# lp-servo12.net
KiCad netlist of a schematic drawn in EAGLE
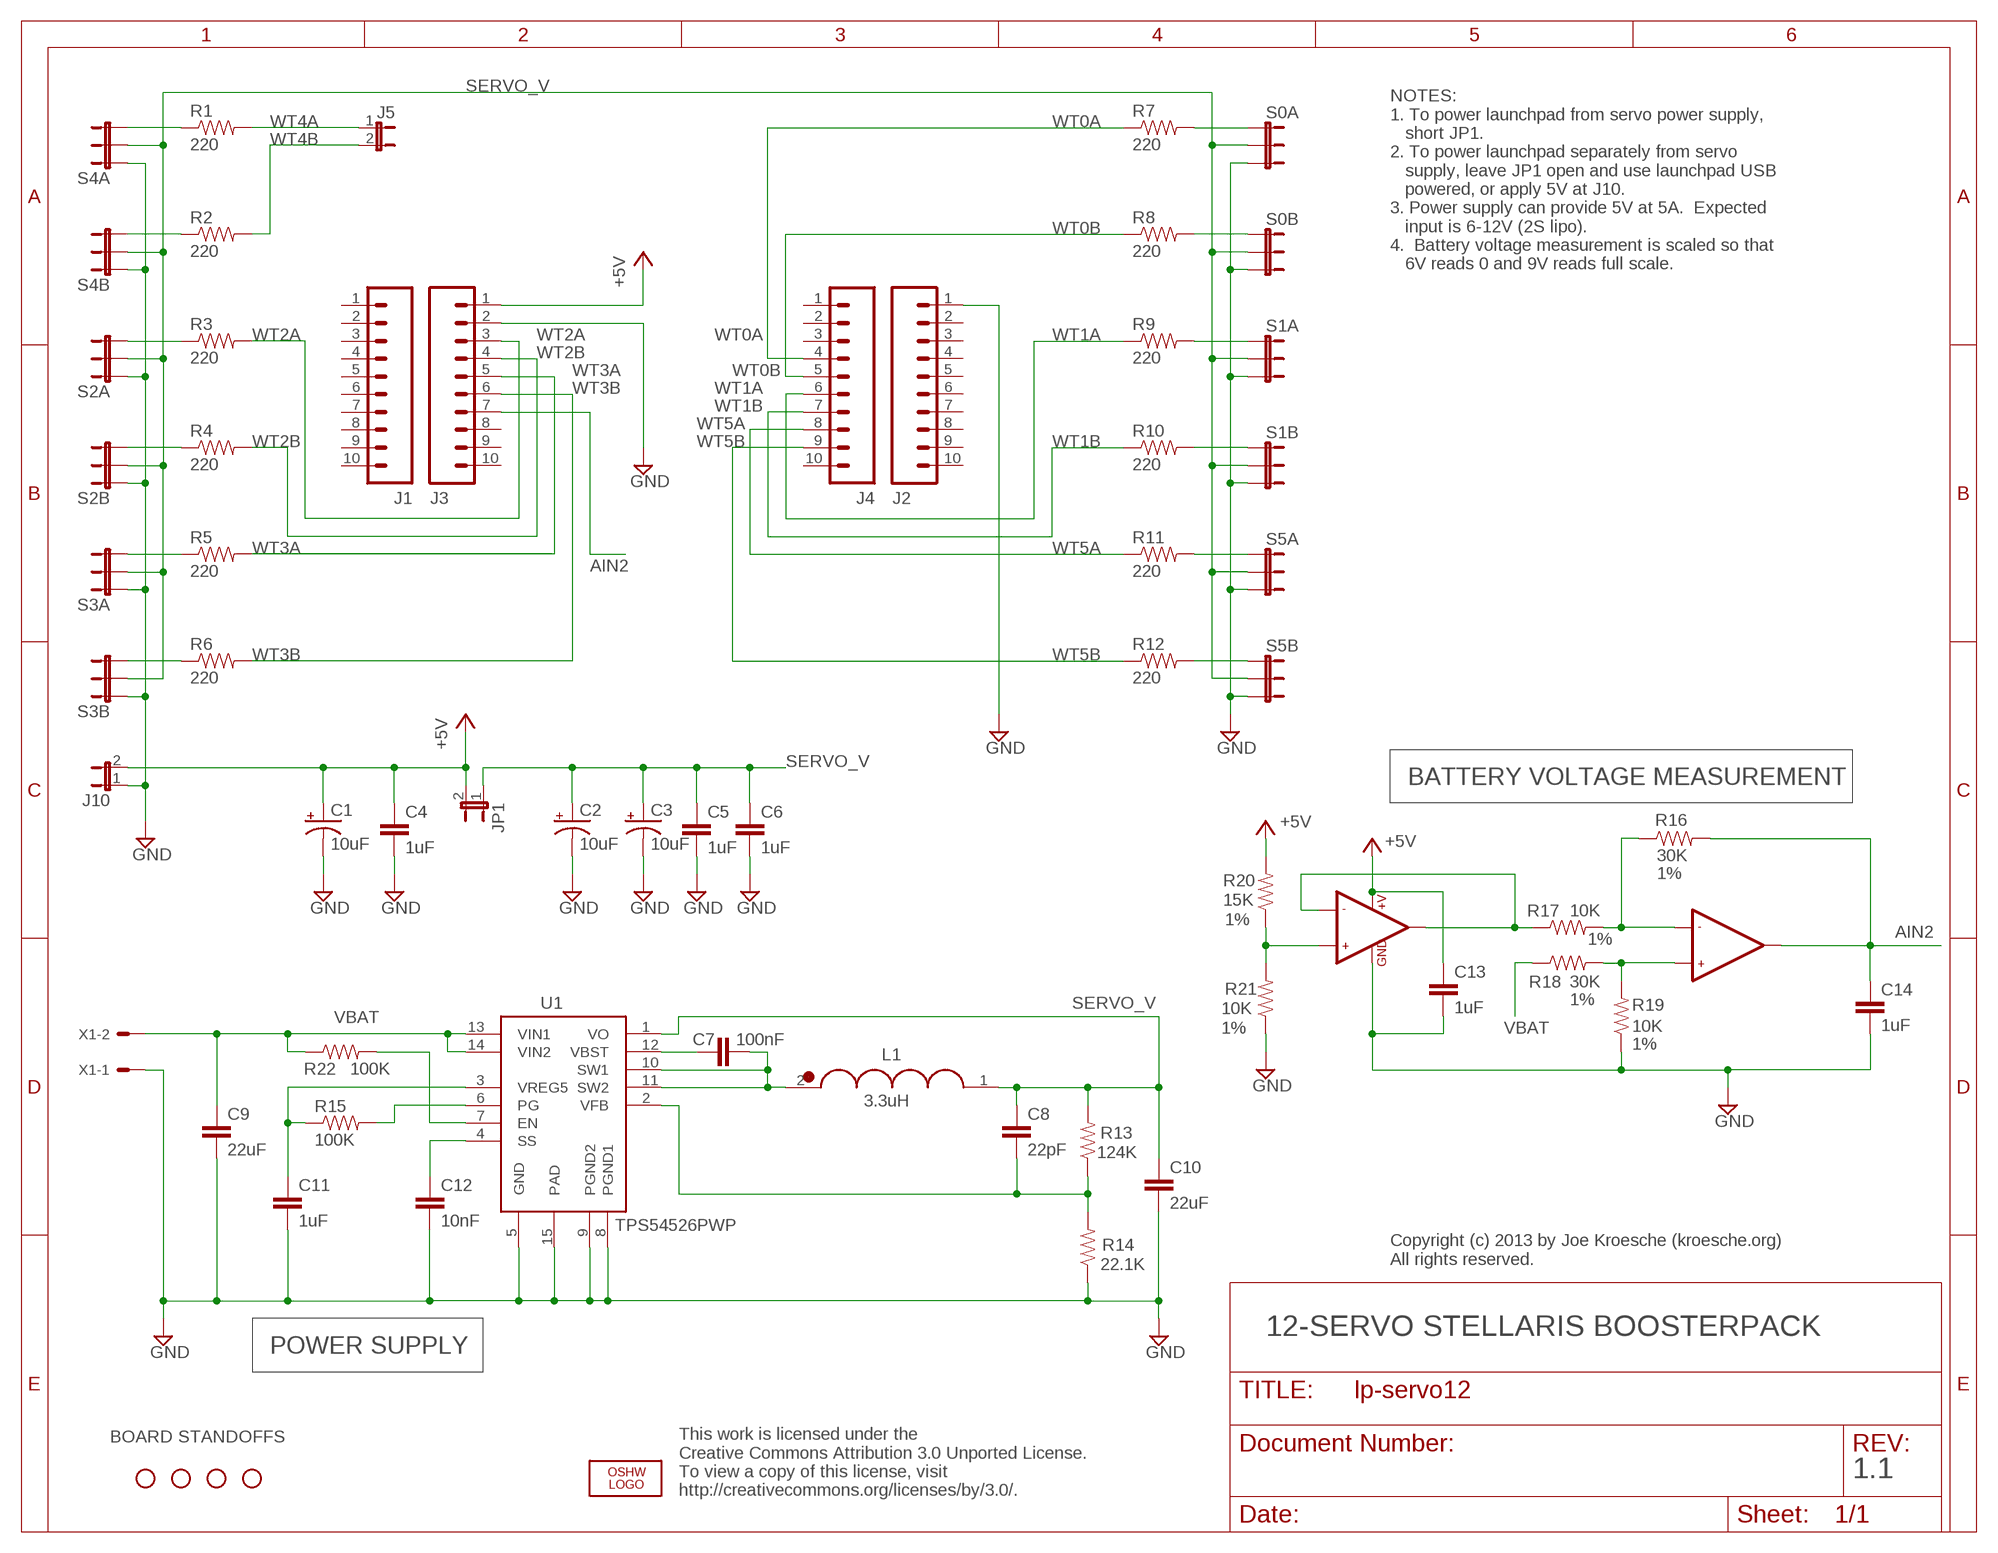
[diagram p0: schematic, sheet 1]

(export (version "E")
  (design (tool "Eeschema 10.0.6"))
  (components
    (comp (ref "C1")
      (value "10uF")
      (footprint "eagle-import:EIA3216")
      (fields (field (name "PARTNO") "CAP_10u_20V_20PCT_1206"))
      (libsource (lib "eagle-import") (part "CAP_POL1206"))
    )
    (comp (ref "C2")
      (value "10uF")
      (footprint "eagle-import:EIA3216")
      (fields (field (name "PARTNO") "CAP_10u_20V_20PCT_1206"))
      (libsource (lib "eagle-import") (part "CAP_POL1206"))
    )
    (comp (ref "C3")
      (value "10uF")
      (footprint "eagle-import:EIA3216")
      (fields (field (name "PARTNO") "CAP_10u_20V_20PCT_1206"))
      (libsource (lib "eagle-import") (part "CAP_POL1206"))
    )
    (comp (ref "C4")
      (value "1uF")
      (footprint "eagle-import:0805")
      (fields (field (name "PARTNO") "CAP_1u_20V_20PCT_0805"))
      (libsource (lib "eagle-import") (part "CAP0805"))
    )
    (comp (ref "C5")
      (value "1uF")
      (footprint "eagle-import:0805")
      (fields (field (name "PARTNO") "CAP_1u_20V_20PCT_0805"))
      (libsource (lib "eagle-import") (part "CAP0805"))
    )
    (comp (ref "C6")
      (value "1uF")
      (footprint "eagle-import:0805")
      (fields (field (name "PARTNO") "CAP_1u_20V_20PCT_0805"))
      (libsource (lib "eagle-import") (part "CAP0805"))
    )
    (comp (ref "C7")
      (value "100nF")
      (footprint "eagle-import:0805")
      (fields (field (name "PARTNO") "CAP_100n_25V_10PCT_0805"))
      (libsource (lib "eagle-import") (part "CAP0805"))
    )
    (comp (ref "C8")
      (value "22pF")
      (footprint "eagle-import:0805")
      (fields (field (name "PARTNO") "CAP_22p_50V_10PCT_0805"))
      (libsource (lib "eagle-import") (part "CAP0805"))
    )
    (comp (ref "C9")
      (value "22uF")
      (footprint "eagle-import:1210")
      (fields (field (name "PARTNO") "CAP_22u_16V_10PCT_1210"))
      (libsource (lib "eagle-import") (part "CAP1210"))
    )
    (comp (ref "C10")
      (value "22uF")
      (footprint "eagle-import:1206")
      (fields (field (name "PARTNO") "CAP_22u_16V_20PCT_1206"))
      (libsource (lib "eagle-import") (part "CAP1206"))
    )
    (comp (ref "C11")
      (value "1uF")
      (footprint "eagle-import:0805")
      (fields (field (name "PARTNO") "CAP_1u_20V_20PCT_0805"))
      (libsource (lib "eagle-import") (part "CAP0805"))
    )
    (comp (ref "C12")
      (value "10nF")
      (footprint "eagle-import:0805")
      (fields (field (name "PARTNO") "CAP_10n_50V_10PCT_0805"))
      (libsource (lib "eagle-import") (part "CAP0805"))
    )
    (comp (ref "C13")
      (value "1uF")
      (footprint "eagle-import:0805")
      (fields (field (name "PARTNO") "CAP_1u_20V_20PCT_0805"))
      (libsource (lib "eagle-import") (part "CAP0805"))
    )
    (comp (ref "C14")
      (value "1uF")
      (footprint "eagle-import:0805")
      (fields (field (name "PARTNO") "CAP_1u_20V_20PCT_0805"))
      (libsource (lib "eagle-import") (part "CAP0805"))
    )
    (comp (ref "J1")
      (value "M10\"")
      (footprint "eagle-import:1X10")
      (fields (field (name "PARTNO") "68002-110HLF"))
      (libsource (lib "eagle-import") (part "M10{dblquote}"))
    )
    (comp (ref "J2")
      (value "M10\"")
      (footprint "eagle-import:1X10")
      (fields (field (name "PARTNO") "68002-110HLF"))
      (libsource (lib "eagle-import") (part "M10{dblquote}"))
    )
    (comp (ref "J3")
      (value "M10\"")
      (footprint "eagle-import:1X10")
      (fields (field (name "PARTNO") "68002-110HLF"))
      (libsource (lib "eagle-import") (part "M10{dblquote}"))
    )
    (comp (ref "J4")
      (value "M10\"")
      (footprint "eagle-import:1X10")
      (fields (field (name "PARTNO") "68002-110HLF"))
      (libsource (lib "eagle-import") (part "M10{dblquote}"))
    )
    (comp (ref "J5")
      (value "JUMPER-2PTH")
      (footprint "eagle-import:1X02")
      (fields (field (name "PARTNO") "68002-202HLF"))
      (libsource (lib "eagle-import") (part "JUMPER-2PTH"))
    )
    (comp (ref "J10")
      (value "JUMPER-2PTH")
      (footprint "eagle-import:1X02")
      (fields (field (name "PARTNO") "68016-402"))
      (libsource (lib "eagle-import") (part "JUMPER-2PTH"))
    )
    (comp (ref "JP1")
      (value "JUMPER-2PTH")
      (footprint "eagle-import:1X02")
      (fields (field (name "PARTNO") "68002-202HLF"))
      (libsource (lib "eagle-import") (part "JUMPER-2PTH"))
    )
    (comp (ref "L1")
      (value "3.3uH")
      (footprint "eagle-import:VISHAY-IHLP3232DZER")
      (fields
        (field (name "MANF") "Vishay/Dale")
        (field (name "MANF#") "IHLP3232DZER3R3M11")
        (field (name "MOUSER#") "70-IHLP3232DZER3R3M11")
        (field (name "PARTNO") "IHLP3232DZER3R3M11")
      )
      (libsource (lib "eagle-import") (part "VISHAY-IHLP-3232DZ-11"))
    )
    (comp (ref "LOGO2")
      (value "OSHW_LOGO_6MILX0200-NT")
      (footprint "eagle-import:OSHW_6X200_NOTEXT")
      (libsource (lib "eagle-import") (part "OSHW_LOGO_6MILX0200-NT"))
    )
    (comp (ref "R1")
      (value "220")
      (footprint "eagle-import:0805")
      (fields (field (name "MANF") "Panasonic") (field (name "PARTNO") "RES_220_20V_10PCT_0805"))
      (libsource (lib "eagle-import") (part "RESISTOR0805-RES"))
    )
    (comp (ref "R2")
      (value "220")
      (footprint "eagle-import:0805")
      (fields (field (name "PARTNO") "RES_220_20V_10PCT_0805"))
      (libsource (lib "eagle-import") (part "RESISTOR0805-RES"))
    )
    (comp (ref "R3")
      (value "220")
      (footprint "eagle-import:0805")
      (fields (field (name "PARTNO") "RES_220_20V_10PCT_0805"))
      (libsource (lib "eagle-import") (part "RESISTOR0805-RES"))
    )
    (comp (ref "R4")
      (value "220")
      (footprint "eagle-import:0805")
      (fields (field (name "PARTNO") "RES_220_20V_10PCT_0805"))
      (libsource (lib "eagle-import") (part "RESISTOR0805-RES"))
    )
    (comp (ref "R5")
      (value "220")
      (footprint "eagle-import:0805")
      (fields (field (name "PARTNO") "RES_220_20V_10PCT_0805"))
      (libsource (lib "eagle-import") (part "RESISTOR0805-RES"))
    )
    (comp (ref "R6")
      (value "220")
      (footprint "eagle-import:0805")
      (fields (field (name "PARTNO") "RES_220_20V_10PCT_0805"))
      (libsource (lib "eagle-import") (part "RESISTOR0805-RES"))
    )
    (comp (ref "R7")
      (value "220")
      (footprint "eagle-import:0805")
      (fields (field (name "PARTNO") "RES_220_20V_10PCT_0805"))
      (libsource (lib "eagle-import") (part "RESISTOR0805-RES"))
    )
    (comp (ref "R8")
      (value "220")
      (footprint "eagle-import:0805")
      (fields (field (name "PARTNO") "RES_220_20V_10PCT_0805"))
      (libsource (lib "eagle-import") (part "RESISTOR0805-RES"))
    )
    (comp (ref "R9")
      (value "220")
      (footprint "eagle-import:0805")
      (fields (field (name "PARTNO") "RES_220_20V_10PCT_0805"))
      (libsource (lib "eagle-import") (part "RESISTOR0805-RES"))
    )
    (comp (ref "R10")
      (value "220")
      (footprint "eagle-import:0805")
      (fields (field (name "PARTNO") "RES_220_20V_10PCT_0805"))
      (libsource (lib "eagle-import") (part "RESISTOR0805-RES"))
    )
    (comp (ref "R11")
      (value "220")
      (footprint "eagle-import:0805")
      (fields (field (name "PARTNO") "RES_220_20V_10PCT_0805"))
      (libsource (lib "eagle-import") (part "RESISTOR0805-RES"))
    )
    (comp (ref "R12")
      (value "220")
      (footprint "eagle-import:0805")
      (fields (field (name "PARTNO") "RES_220_20V_10PCT_0805"))
      (libsource (lib "eagle-import") (part "RESISTOR0805-RES"))
    )
    (comp (ref "R13")
      (value "124K")
      (footprint "eagle-import:0805")
      (fields (field (name "PARTNO") "RES_124K_20V_1PCT_0805"))
      (libsource (lib "eagle-import") (part "RESISTOR0805-RES"))
    )
    (comp (ref "R14")
      (value "22.1K")
      (footprint "eagle-import:0805")
      (fields (field (name "PARTNO") "RES_22.1K_20V_1PCT_0805"))
      (libsource (lib "eagle-import") (part "RESISTOR0805-RES"))
    )
    (comp (ref "R15")
      (value "100K")
      (footprint "eagle-import:0805")
      (fields (field (name "PARTNO") "RES_100K_20V_1PCT_0805"))
      (libsource (lib "eagle-import") (part "RESISTOR0805-RES"))
    )
    (comp (ref "R16")
      (value "30K")
      (footprint "eagle-import:0805")
      (fields (field (name "PARTNO") "RES_30K_20V_1PCT_0805") (field (name "TOL") "1%"))
      (libsource (lib "eagle-import") (part "RESISTOR0805-RES"))
    )
    (comp (ref "R17")
      (value "10K")
      (footprint "eagle-import:0805")
      (fields (field (name "PARTNO") "RES_10K_20V_1PCT_0805") (field (name "TOL") "1%"))
      (libsource (lib "eagle-import") (part "RESISTOR0805-RES"))
    )
    (comp (ref "R18")
      (value "30K")
      (footprint "eagle-import:0805")
      (fields (field (name "PARTNO") "RES_30K_20V_1PCT_0805") (field (name "TOL") "1%"))
      (libsource (lib "eagle-import") (part "RESISTOR0805-RES"))
    )
    (comp (ref "R19")
      (value "10K")
      (footprint "eagle-import:0805")
      (fields (field (name "PARTNO") "RES_10K_20V_1PCT_0805") (field (name "TOL") "1%"))
      (libsource (lib "eagle-import") (part "RESISTOR0805-RES"))
    )
    (comp (ref "R20")
      (value "15K")
      (footprint "eagle-import:0805")
      (fields (field (name "PARTNO") "RES_15K_20V_1PCT_0805") (field (name "TOL") "1%"))
      (libsource (lib "eagle-import") (part "RESISTOR0805-RES"))
    )
    (comp (ref "R21")
      (value "10K")
      (footprint "eagle-import:0805")
      (fields (field (name "PARTNO") "RES_10K_20V_1PCT_0805") (field (name "TOL") "1%"))
      (libsource (lib "eagle-import") (part "RESISTOR0805-RES"))
    )
    (comp (ref "R22")
      (value "100K")
      (footprint "eagle-import:0805")
      (fields (field (name "PARTNO") "RES_100K_20V_1PCT_0805"))
      (libsource (lib "eagle-import") (part "RESISTOR0805-RES"))
    )
    (comp (ref "S0A")
      (value "JUMPER-3PTH")
      (footprint "eagle-import:1X03")
      (fields (field (name "PARTNO") "68002-403HLF"))
      (libsource (lib "eagle-import") (part "JUMPER-3PTH"))
    )
    (comp (ref "S0B")
      (value "JUMPER-3PTH")
      (footprint "eagle-import:1X03")
      (fields (field (name "PARTNO") "68002-403HLF"))
      (libsource (lib "eagle-import") (part "JUMPER-3PTH"))
    )
    (comp (ref "S1A")
      (value "JUMPER-3PTH")
      (footprint "eagle-import:1X03")
      (fields (field (name "PARTNO") "68002-403HLF"))
      (libsource (lib "eagle-import") (part "JUMPER-3PTH"))
    )
    (comp (ref "S1B")
      (value "JUMPER-3PTH")
      (footprint "eagle-import:1X03")
      (fields (field (name "PARTNO") "68002-403HLF"))
      (libsource (lib "eagle-import") (part "JUMPER-3PTH"))
    )
    (comp (ref "S2A")
      (value "JUMPER-3PTH")
      (footprint "eagle-import:1X03")
      (fields (field (name "PARTNO") "68002-403HLF"))
      (libsource (lib "eagle-import") (part "JUMPER-3PTH"))
    )
    (comp (ref "S2B")
      (value "JUMPER-3PTH")
      (footprint "eagle-import:1X03")
      (fields (field (name "PARTNO") "68002-403HLF"))
      (libsource (lib "eagle-import") (part "JUMPER-3PTH"))
    )
    (comp (ref "S3A")
      (value "JUMPER-3PTH")
      (footprint "eagle-import:1X03")
      (fields (field (name "PARTNO") "68002-403HLF"))
      (libsource (lib "eagle-import") (part "JUMPER-3PTH"))
    )
    (comp (ref "S3B")
      (value "JUMPER-3PTH")
      (footprint "eagle-import:1X03")
      (fields (field (name "PARTNO") "68002-403HLF"))
      (libsource (lib "eagle-import") (part "JUMPER-3PTH"))
    )
    (comp (ref "S4A")
      (value "JUMPER-3PTH")
      (footprint "eagle-import:1X03")
      (fields (field (name "PARTNO") "68002-403HLF"))
      (libsource (lib "eagle-import") (part "JUMPER-3PTH"))
    )
    (comp (ref "S4B")
      (value "JUMPER-3PTH")
      (footprint "eagle-import:1X03")
      (fields (field (name "PARTNO") "68002-403HLF"))
      (libsource (lib "eagle-import") (part "JUMPER-3PTH"))
    )
    (comp (ref "S5A")
      (value "JUMPER-3PTH")
      (footprint "eagle-import:1X03")
      (fields (field (name "PARTNO") "68002-403HLF"))
      (libsource (lib "eagle-import") (part "JUMPER-3PTH"))
    )
    (comp (ref "S5B")
      (value "JUMPER-3PTH")
      (footprint "eagle-import:1X03")
      (fields (field (name "PARTNO") "68002-403HLF"))
      (libsource (lib "eagle-import") (part "JUMPER-3PTH"))
    )
    (comp (ref "STANDOFF1")
      (value "STAND-OFF")
      (footprint "eagle-import:STAND-OFF")
      (libsource (lib "eagle-import") (part "STAND-OFF"))
    )
    (comp (ref "STANDOFF2")
      (value "STAND-OFF")
      (footprint "eagle-import:STAND-OFF")
      (libsource (lib "eagle-import") (part "STAND-OFF"))
    )
    (comp (ref "STANDOFF3")
      (value "STAND-OFF")
      (footprint "eagle-import:STAND-OFF")
      (libsource (lib "eagle-import") (part "STAND-OFF"))
    )
    (comp (ref "STANDOFF4")
      (value "STAND-OFF")
      (footprint "eagle-import:STAND-OFF")
      (libsource (lib "eagle-import") (part "STAND-OFF"))
    )
    (comp (ref "U1")
      (value "TPS54526PWP")
      (footprint "eagle-import:PWP-R-PDSO-G14")
      (fields (field (name "MANF") "Texas Instruments"))
      (libsource (lib "eagle-import") (part "TPS54526PWP"))
    )
    (comp (ref "U2")
      (value "LMV358")
      (footprint "eagle-import:SO08")
      (fields
        (field (name "MANF") "Texas Instruments")
        (field (name "MANF#") "LMV358QDR")
        (field (name "MOUSER#") "595-LMV358QDR")
        (field (name "PARTNO") "LMV358QDR")
      )
      (libsource (lib "eagle-import") (part "LMV358"))
    )
    (comp (ref "X1")
      (value "KK-156-2")
      (footprint "eagle-import:KK-156-2")
      (fields
        (field (name "MANF") "Molex")
        (field (name "PARTNO") "KK-156-2-LOCK-RTANGLE")
        (field (name "MANF#") "76650-0208")
        (field (name "MOUSER#") "538-76650-0208")
      )
      (libsource (lib "eagle-import") (part "KK-156-2"))
    )
  )
  (nets
    (net (code "1") (name "+5V") (class "Default")
      (node (ref "C1") (pin "A") (pinfunction "+_A") (pintype "passive"))
      (node (ref "C13") (pin "1") (pinfunction "1_1") (pintype "passive"))
      (node (ref "C4") (pin "1") (pinfunction "1_1") (pintype "passive"))
      (node (ref "J10") (pin "2") (pinfunction "2_2") (pintype "passive"))
      (node (ref "J3") (pin "1") (pinfunction "1_1") (pintype "passive"))
      (node (ref "JP1") (pin "2") (pinfunction "2_2") (pintype "passive"))
      (node (ref "R20") (pin "2") (pinfunction "2_2") (pintype "passive"))
      (node (ref "U2") (pin "8") (pinfunction "+V_8") (pintype "power_in"))
    )
    (net (code "2") (name "/AIN2") (class "Default")
      (node (ref "C14") (pin "1") (pinfunction "1_1") (pintype "passive"))
      (node (ref "J3") (pin "7") (pinfunction "7_7") (pintype "passive"))
      (node (ref "R16") (pin "2") (pinfunction "2_2") (pintype "passive"))
      (node (ref "U2") (pin "7") (pinfunction "OUT2_7") (pintype "output"))
    )
    (net (code "3") (name "/SERVO_V") (class "Default")
      (node (ref "C10") (pin "1") (pinfunction "1_1") (pintype "passive"))
      (node (ref "C2") (pin "A") (pinfunction "+_A") (pintype "passive"))
      (node (ref "C3") (pin "A") (pinfunction "+_A") (pintype "passive"))
      (node (ref "C5") (pin "1") (pinfunction "1_1") (pintype "passive"))
      (node (ref "C6") (pin "1") (pinfunction "1_1") (pintype "passive"))
      (node (ref "C8") (pin "1") (pinfunction "1_1") (pintype "passive"))
      (node (ref "JP1") (pin "1") (pinfunction "1_1") (pintype "passive"))
      (node (ref "L1") (pin "1") (pinfunction "NEG_1") (pintype "passive"))
      (node (ref "R13") (pin "2") (pinfunction "2_2") (pintype "passive"))
      (node (ref "S0A") (pin "2") (pinfunction "2_2") (pintype "passive"))
      (node (ref "S0B") (pin "2") (pinfunction "2_2") (pintype "passive"))
      (node (ref "S1A") (pin "2") (pinfunction "2_2") (pintype "passive"))
      (node (ref "S1B") (pin "2") (pinfunction "2_2") (pintype "passive"))
      (node (ref "S2A") (pin "2") (pinfunction "2_2") (pintype "passive"))
      (node (ref "S2B") (pin "2") (pinfunction "2_2") (pintype "passive"))
      (node (ref "S3A") (pin "2") (pinfunction "2_2") (pintype "passive"))
      (node (ref "S3B") (pin "2") (pinfunction "2_2") (pintype "passive"))
      (node (ref "S4A") (pin "2") (pinfunction "2_2") (pintype "passive"))
      (node (ref "S4B") (pin "2") (pinfunction "2_2") (pintype "passive"))
      (node (ref "S5A") (pin "2") (pinfunction "2_2") (pintype "passive"))
      (node (ref "S5B") (pin "2") (pinfunction "2_2") (pintype "passive"))
      (node (ref "U1") (pin "1") (pinfunction "VO_1") (pintype "power_in"))
    )
    (net (code "4") (name "/VBAT") (class "Default")
      (node (ref "C9") (pin "1") (pinfunction "1_1") (pintype "passive"))
      (node (ref "R18") (pin "1") (pinfunction "1_1") (pintype "passive"))
      (node (ref "R22") (pin "1") (pinfunction "1_1") (pintype "passive"))
      (node (ref "U1") (pin "13") (pinfunction "VIN1_13") (pintype "power_in"))
      (node (ref "U1") (pin "14") (pinfunction "VIN2_14") (pintype "power_in"))
      (node (ref "X1") (pin "2") (pinfunction "S_2") (pintype "passive"))
    )
    (net (code "5") (name "/WT0A") (class "Default")
      (node (ref "J4") (pin "4") (pinfunction "4_4") (pintype "passive"))
      (node (ref "R7") (pin "1") (pinfunction "1_1") (pintype "passive"))
    )
    (net (code "6") (name "/WT0B") (class "Default")
      (node (ref "J4") (pin "5") (pinfunction "5_5") (pintype "passive"))
      (node (ref "R8") (pin "1") (pinfunction "1_1") (pintype "passive"))
    )
    (net (code "7") (name "/WT1A") (class "Default")
      (node (ref "J4") (pin "6") (pinfunction "6_6") (pintype "passive"))
      (node (ref "R9") (pin "1") (pinfunction "1_1") (pintype "passive"))
    )
    (net (code "8") (name "/WT1B") (class "Default")
      (node (ref "J4") (pin "7") (pinfunction "7_7") (pintype "passive"))
      (node (ref "R10") (pin "1") (pinfunction "1_1") (pintype "passive"))
    )
    (net (code "9") (name "/WT2A") (class "Default")
      (node (ref "J3") (pin "3") (pinfunction "3_3") (pintype "passive"))
      (node (ref "R3") (pin "2") (pinfunction "2_2") (pintype "passive"))
    )
    (net (code "10") (name "/WT2B") (class "Default")
      (node (ref "J3") (pin "4") (pinfunction "4_4") (pintype "passive"))
      (node (ref "R4") (pin "2") (pinfunction "2_2") (pintype "passive"))
    )
    (net (code "11") (name "/WT3A") (class "Default")
      (node (ref "J3") (pin "5") (pinfunction "5_5") (pintype "passive"))
      (node (ref "R5") (pin "2") (pinfunction "2_2") (pintype "passive"))
    )
    (net (code "12") (name "/WT3B") (class "Default")
      (node (ref "J3") (pin "6") (pinfunction "6_6") (pintype "passive"))
      (node (ref "R6") (pin "2") (pinfunction "2_2") (pintype "passive"))
    )
    (net (code "13") (name "/WT4A") (class "Default")
      (node (ref "J5") (pin "1") (pinfunction "1_1") (pintype "passive"))
      (node (ref "R1") (pin "2") (pinfunction "2_2") (pintype "passive"))
    )
    (net (code "14") (name "/WT4B") (class "Default")
      (node (ref "J5") (pin "2") (pinfunction "2_2") (pintype "passive"))
      (node (ref "R2") (pin "2") (pinfunction "2_2") (pintype "passive"))
    )
    (net (code "15") (name "/WT5A") (class "Default")
      (node (ref "J4") (pin "8") (pinfunction "8_8") (pintype "passive"))
      (node (ref "R11") (pin "1") (pinfunction "1_1") (pintype "passive"))
    )
    (net (code "16") (name "/WT5B") (class "Default")
      (node (ref "J4") (pin "9") (pinfunction "9_9") (pintype "passive"))
      (node (ref "R12") (pin "1") (pinfunction "1_1") (pintype "passive"))
    )
    (net (code "17") (name "GND") (class "Default")
      (node (ref "C1") (pin "C") (pinfunction "-_C") (pintype "passive"))
      (node (ref "C10") (pin "2") (pinfunction "2_2") (pintype "passive"))
      (node (ref "C11") (pin "2") (pinfunction "2_2") (pintype "passive"))
      (node (ref "C12") (pin "2") (pinfunction "2_2") (pintype "passive"))
      (node (ref "C13") (pin "2") (pinfunction "2_2") (pintype "passive"))
      (node (ref "C14") (pin "2") (pinfunction "2_2") (pintype "passive"))
      (node (ref "C2") (pin "C") (pinfunction "-_C") (pintype "passive"))
      (node (ref "C3") (pin "C") (pinfunction "-_C") (pintype "passive"))
      (node (ref "C4") (pin "2") (pinfunction "2_2") (pintype "passive"))
      (node (ref "C5") (pin "2") (pinfunction "2_2") (pintype "passive"))
      (node (ref "C6") (pin "2") (pinfunction "2_2") (pintype "passive"))
      (node (ref "C9") (pin "2") (pinfunction "2_2") (pintype "passive"))
      (node (ref "J10") (pin "1") (pinfunction "1_1") (pintype "passive"))
      (node (ref "J2") (pin "1") (pinfunction "1_1") (pintype "passive"))
      (node (ref "J3") (pin "2") (pinfunction "2_2") (pintype "passive"))
      (node (ref "R14") (pin "1") (pinfunction "1_1") (pintype "passive"))
      (node (ref "R19") (pin "1") (pinfunction "1_1") (pintype "passive"))
      (node (ref "R21") (pin "1") (pinfunction "1_1") (pintype "passive"))
      (node (ref "S0A") (pin "3") (pinfunction "3_3") (pintype "passive"))
      (node (ref "S0B") (pin "3") (pinfunction "3_3") (pintype "passive"))
      (node (ref "S1A") (pin "3") (pinfunction "3_3") (pintype "passive"))
      (node (ref "S1B") (pin "3") (pinfunction "3_3") (pintype "passive"))
      (node (ref "S2A") (pin "1") (pinfunction "1_1") (pintype "passive"))
      (node (ref "S2B") (pin "1") (pinfunction "1_1") (pintype "passive"))
      (node (ref "S3A") (pin "1") (pinfunction "1_1") (pintype "passive"))
      (node (ref "S3B") (pin "1") (pinfunction "1_1") (pintype "passive"))
      (node (ref "S4A") (pin "1") (pinfunction "1_1") (pintype "passive"))
      (node (ref "S4B") (pin "1") (pinfunction "1_1") (pintype "passive"))
      (node (ref "S5A") (pin "3") (pinfunction "3_3") (pintype "passive"))
      (node (ref "S5B") (pin "3") (pinfunction "3_3") (pintype "passive"))
      (node (ref "U1") (pin "15") (pinfunction "PAD_15") (pintype "power_in"))
      (node (ref "U1") (pin "5") (pinfunction "GND_5") (pintype "power_in"))
      (node (ref "U1") (pin "8") (pinfunction "PGND1_8") (pintype "power_in"))
      (node (ref "U1") (pin "9") (pinfunction "PGND2_9") (pintype "power_in"))
      (node (ref "U2") (pin "4") (pinfunction "GND_4") (pintype "power_in"))
      (node (ref "X1") (pin "1") (pinfunction "S_1") (pintype "passive"))
    )
    (net (code "18") (name "Net-(L1-POS)") (class "Default")
      (node (ref "C7") (pin "2") (pinfunction "2_2") (pintype "passive"))
      (node (ref "L1") (pin "2") (pinfunction "POS_2") (pintype "passive"))
      (node (ref "U1") (pin "10") (pinfunction "SW1_10") (pintype "bidirectional"))
      (node (ref "U1") (pin "11") (pinfunction "SW2_11") (pintype "bidirectional"))
    )
    (net (code "19") (name "Net-(R1-Pad1)") (class "Default")
      (node (ref "R1") (pin "1") (pinfunction "1_1") (pintype "passive"))
      (node (ref "S4A") (pin "3") (pinfunction "3_3") (pintype "passive"))
    )
    (net (code "20") (name "Net-(R2-Pad1)") (class "Default")
      (node (ref "R2") (pin "1") (pinfunction "1_1") (pintype "passive"))
      (node (ref "S4B") (pin "3") (pinfunction "3_3") (pintype "passive"))
    )
    (net (code "21") (name "Net-(R3-Pad1)") (class "Default")
      (node (ref "R3") (pin "1") (pinfunction "1_1") (pintype "passive"))
      (node (ref "S2A") (pin "3") (pinfunction "3_3") (pintype "passive"))
    )
    (net (code "22") (name "Net-(R4-Pad1)") (class "Default")
      (node (ref "R4") (pin "1") (pinfunction "1_1") (pintype "passive"))
      (node (ref "S2B") (pin "3") (pinfunction "3_3") (pintype "passive"))
    )
    (net (code "23") (name "Net-(R5-Pad1)") (class "Default")
      (node (ref "R5") (pin "1") (pinfunction "1_1") (pintype "passive"))
      (node (ref "S3A") (pin "3") (pinfunction "3_3") (pintype "passive"))
    )
    (net (code "24") (name "Net-(R6-Pad1)") (class "Default")
      (node (ref "R6") (pin "1") (pinfunction "1_1") (pintype "passive"))
      (node (ref "S3B") (pin "3") (pinfunction "3_3") (pintype "passive"))
    )
    (net (code "25") (name "Net-(R7-Pad2)") (class "Default")
      (node (ref "R7") (pin "2") (pinfunction "2_2") (pintype "passive"))
      (node (ref "S0A") (pin "1") (pinfunction "1_1") (pintype "passive"))
    )
    (net (code "26") (name "Net-(R8-Pad2)") (class "Default")
      (node (ref "R8") (pin "2") (pinfunction "2_2") (pintype "passive"))
      (node (ref "S0B") (pin "1") (pinfunction "1_1") (pintype "passive"))
    )
    (net (code "27") (name "Net-(R9-Pad2)") (class "Default")
      (node (ref "R9") (pin "2") (pinfunction "2_2") (pintype "passive"))
      (node (ref "S1A") (pin "1") (pinfunction "1_1") (pintype "passive"))
    )
    (net (code "28") (name "Net-(R10-Pad2)") (class "Default")
      (node (ref "R10") (pin "2") (pinfunction "2_2") (pintype "passive"))
      (node (ref "S1B") (pin "1") (pinfunction "1_1") (pintype "passive"))
    )
    (net (code "29") (name "Net-(R11-Pad2)") (class "Default")
      (node (ref "R11") (pin "2") (pinfunction "2_2") (pintype "passive"))
      (node (ref "S5A") (pin "1") (pinfunction "1_1") (pintype "passive"))
    )
    (net (code "30") (name "Net-(R12-Pad2)") (class "Default")
      (node (ref "R12") (pin "2") (pinfunction "2_2") (pintype "passive"))
      (node (ref "S5B") (pin "1") (pinfunction "1_1") (pintype "passive"))
    )
    (net (code "31") (name "Net-(U1-EN)") (class "Default")
      (node (ref "R22") (pin "2") (pinfunction "2_2") (pintype "passive"))
      (node (ref "U1") (pin "7") (pinfunction "EN_7") (pintype "bidirectional"))
    )
    (net (code "32") (name "Net-(U1-PG)") (class "Default")
      (node (ref "R15") (pin "2") (pinfunction "2_2") (pintype "passive"))
      (node (ref "U1") (pin "6") (pinfunction "PG_6") (pintype "bidirectional"))
    )
    (net (code "33") (name "Net-(U1-SS)") (class "Default")
      (node (ref "C12") (pin "1") (pinfunction "1_1") (pintype "passive"))
      (node (ref "U1") (pin "4") (pinfunction "SS_4") (pintype "bidirectional"))
    )
    (net (code "34") (name "Net-(U1-VBST)") (class "Default")
      (node (ref "C7") (pin "1") (pinfunction "1_1") (pintype "passive"))
      (node (ref "U1") (pin "12") (pinfunction "VBST_12") (pintype "bidirectional"))
    )
    (net (code "35") (name "Net-(U1-VFB)") (class "Default")
      (node (ref "C8") (pin "2") (pinfunction "2_2") (pintype "passive"))
      (node (ref "R13") (pin "1") (pinfunction "1_1") (pintype "passive"))
      (node (ref "R14") (pin "2") (pinfunction "2_2") (pintype "passive"))
      (node (ref "U1") (pin "2") (pinfunction "VFB_2") (pintype "bidirectional"))
    )
    (net (code "36") (name "Net-(U1-VREG5)") (class "Default")
      (node (ref "C11") (pin "1") (pinfunction "1_1") (pintype "passive"))
      (node (ref "R15") (pin "1") (pinfunction "1_1") (pintype "passive"))
      (node (ref "U1") (pin "3") (pinfunction "VREG5_3") (pintype "bidirectional"))
    )
    (net (code "37") (name "Net-(U2A-+IN1)") (class "Default")
      (node (ref "R20") (pin "1") (pinfunction "1_1") (pintype "passive"))
      (node (ref "R21") (pin "2") (pinfunction "2_2") (pintype "passive"))
      (node (ref "U2") (pin "3") (pinfunction "+IN1_3") (pintype "input"))
    )
    (net (code "38") (name "Net-(U2A--IN1)") (class "Default")
      (node (ref "R17") (pin "1") (pinfunction "1_1") (pintype "passive"))
      (node (ref "U2") (pin "1") (pinfunction "OUT1_1") (pintype "output"))
      (node (ref "U2") (pin "2") (pinfunction "-IN1_2") (pintype "input"))
    )
    (net (code "39") (name "Net-(U2B-+IN2)") (class "Default")
      (node (ref "R18") (pin "2") (pinfunction "2_2") (pintype "passive"))
      (node (ref "R19") (pin "2") (pinfunction "2_2") (pintype "passive"))
      (node (ref "U2") (pin "5") (pinfunction "+IN2_5") (pintype "input"))
    )
    (net (code "40") (name "Net-(U2B--IN2)") (class "Default")
      (node (ref "R16") (pin "1") (pinfunction "1_1") (pintype "passive"))
      (node (ref "R17") (pin "2") (pinfunction "2_2") (pintype "passive"))
      (node (ref "U2") (pin "6") (pinfunction "-IN2_6") (pintype "input"))
    )
    (net (code "41") (name "unconnected-(J1-Pad1)") (class "Default")
      (node (ref "J1") (pin "1") (pinfunction "1_1") (pintype "passive"))
    )
    (net (code "42") (name "unconnected-(J1-Pad2)") (class "Default")
      (node (ref "J1") (pin "2") (pinfunction "2_2") (pintype "passive"))
    )
    (net (code "43") (name "unconnected-(J1-Pad3)") (class "Default")
      (node (ref "J1") (pin "3") (pinfunction "3_3") (pintype "passive"))
    )
    (net (code "44") (name "unconnected-(J1-Pad4)") (class "Default")
      (node (ref "J1") (pin "4") (pinfunction "4_4") (pintype "passive"))
    )
    (net (code "45") (name "unconnected-(J1-Pad5)") (class "Default")
      (node (ref "J1") (pin "5") (pinfunction "5_5") (pintype "passive"))
    )
    (net (code "46") (name "unconnected-(J1-Pad6)") (class "Default")
      (node (ref "J1") (pin "6") (pinfunction "6_6") (pintype "passive"))
    )
    (net (code "47") (name "unconnected-(J1-Pad7)") (class "Default")
      (node (ref "J1") (pin "7") (pinfunction "7_7") (pintype "passive"))
    )
    (net (code "48") (name "unconnected-(J1-Pad8)") (class "Default")
      (node (ref "J1") (pin "8") (pinfunction "8_8") (pintype "passive"))
    )
    (net (code "49") (name "unconnected-(J1-Pad9)") (class "Default")
      (node (ref "J1") (pin "9") (pinfunction "9_9") (pintype "passive"))
    )
    (net (code "50") (name "unconnected-(J1-Pad10)") (class "Default")
      (node (ref "J1") (pin "10") (pinfunction "10_10") (pintype "passive"))
    )
    (net (code "51") (name "unconnected-(J2-Pad2)") (class "Default")
      (node (ref "J2") (pin "2") (pinfunction "2_2") (pintype "passive"))
    )
    (net (code "52") (name "unconnected-(J2-Pad3)") (class "Default")
      (node (ref "J2") (pin "3") (pinfunction "3_3") (pintype "passive"))
    )
    (net (code "53") (name "unconnected-(J2-Pad4)") (class "Default")
      (node (ref "J2") (pin "4") (pinfunction "4_4") (pintype "passive"))
    )
    (net (code "54") (name "unconnected-(J2-Pad5)") (class "Default")
      (node (ref "J2") (pin "5") (pinfunction "5_5") (pintype "passive"))
    )
    (net (code "55") (name "unconnected-(J2-Pad6)") (class "Default")
      (node (ref "J2") (pin "6") (pinfunction "6_6") (pintype "passive"))
    )
    (net (code "56") (name "unconnected-(J2-Pad7)") (class "Default")
      (node (ref "J2") (pin "7") (pinfunction "7_7") (pintype "passive"))
    )
    (net (code "57") (name "unconnected-(J2-Pad8)") (class "Default")
      (node (ref "J2") (pin "8") (pinfunction "8_8") (pintype "passive"))
    )
    (net (code "58") (name "unconnected-(J2-Pad9)") (class "Default")
      (node (ref "J2") (pin "9") (pinfunction "9_9") (pintype "passive"))
    )
    (net (code "59") (name "unconnected-(J2-Pad10)") (class "Default")
      (node (ref "J2") (pin "10") (pinfunction "10_10") (pintype "passive"))
    )
    (net (code "60") (name "unconnected-(J3-Pad8)") (class "Default")
      (node (ref "J3") (pin "8") (pinfunction "8_8") (pintype "passive"))
    )
    (net (code "61") (name "unconnected-(J3-Pad9)") (class "Default")
      (node (ref "J3") (pin "9") (pinfunction "9_9") (pintype "passive"))
    )
    (net (code "62") (name "unconnected-(J3-Pad10)") (class "Default")
      (node (ref "J3") (pin "10") (pinfunction "10_10") (pintype "passive"))
    )
    (net (code "63") (name "unconnected-(J4-Pad1)") (class "Default")
      (node (ref "J4") (pin "1") (pinfunction "1_1") (pintype "passive"))
    )
    (net (code "64") (name "unconnected-(J4-Pad2)") (class "Default")
      (node (ref "J4") (pin "2") (pinfunction "2_2") (pintype "passive"))
    )
    (net (code "65") (name "unconnected-(J4-Pad3)") (class "Default")
      (node (ref "J4") (pin "3") (pinfunction "3_3") (pintype "passive"))
    )
    (net (code "66") (name "unconnected-(J4-Pad10)") (class "Default")
      (node (ref "J4") (pin "10") (pinfunction "10_10") (pintype "passive"))
    )
  )
)
